# SCH_RAK_Power_module_2023-06-18.net
KiCad netlist of a schematic drawn in EasyEDA
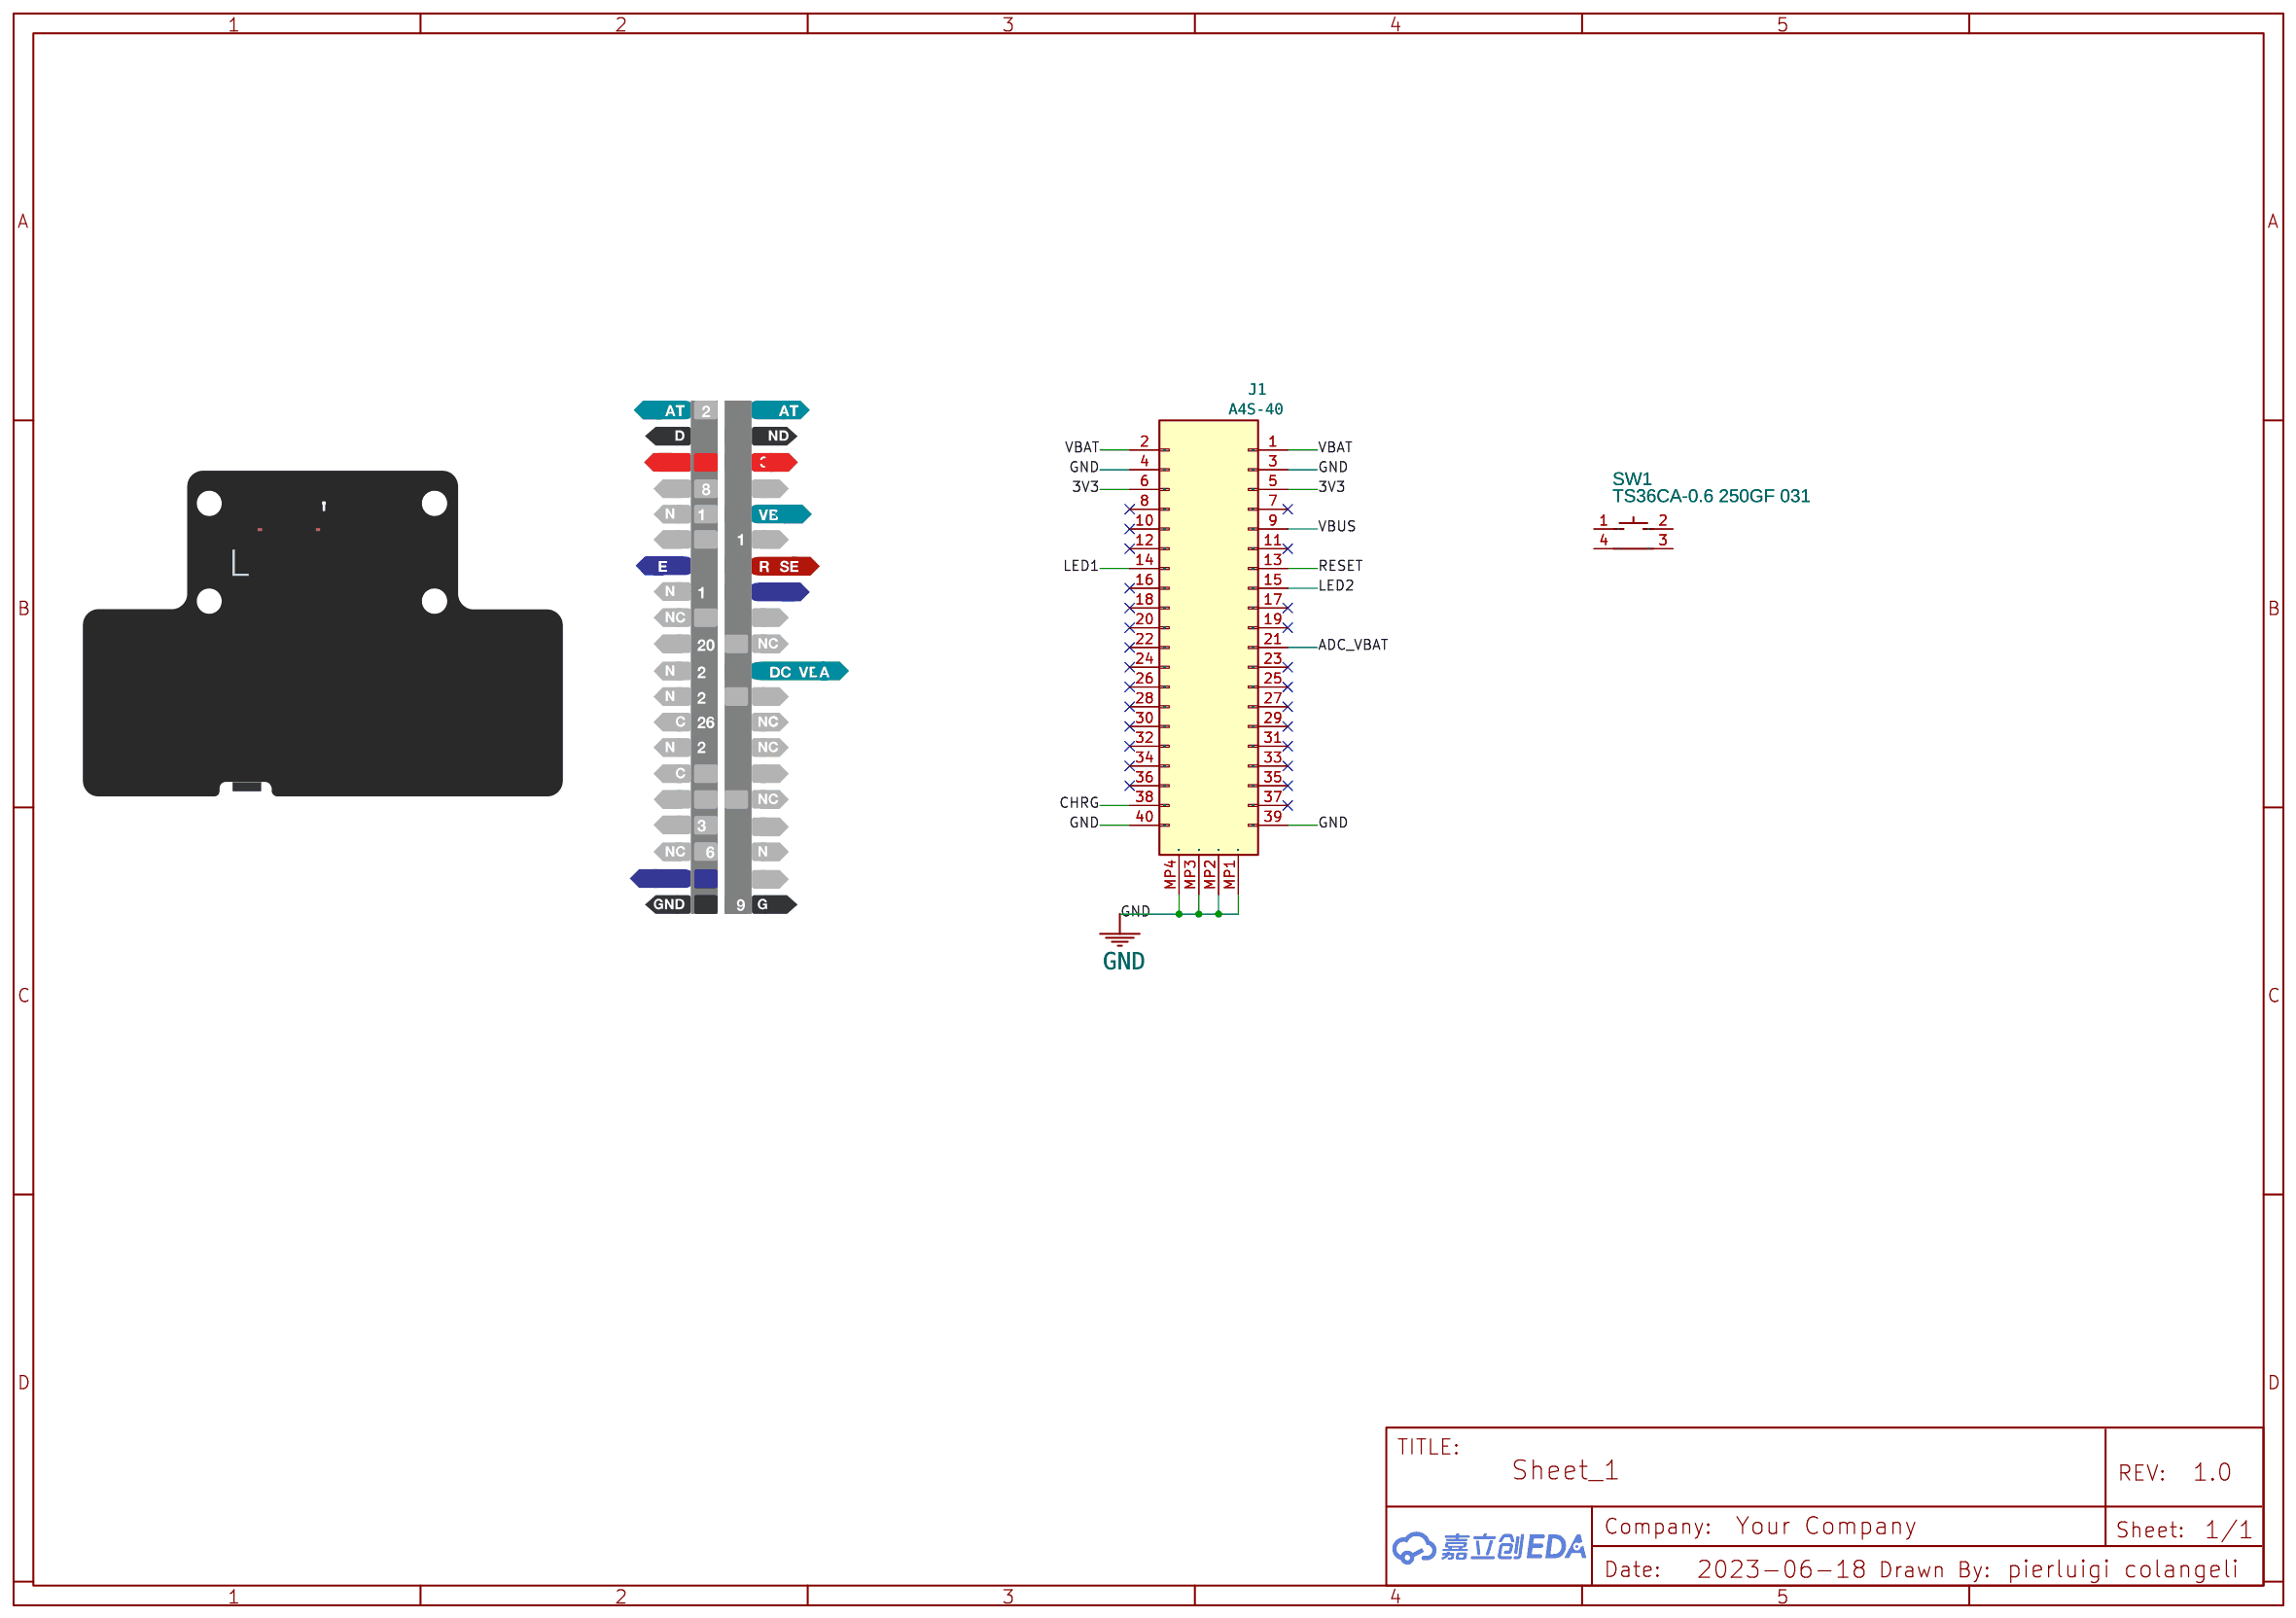
[diagram p0: schematic sheet]

(export (version "E")
  (design (tool "Eeschema 10.0.6"))
  (components
    (comp (ref "J1") (value "A4S-40") (libsource (lib "") (part "Unknown_605_-485")))
    (comp (ref "SW1")
      (value "TS36CA-0.6 250GF 031")
      (fields
        (field (name "BOM_Manufacturer Part") "TS36CA-0.6 250gf 031")
        (field (name "BOM_Supplier Part") "C2906288")
      )
      (libsource (lib "") (part "TS36CA-0.6 250GF 031"))
    )
  )
  (nets
    (net (code "1") (name "/3V3") (class "Default")
      (node (ref "J1") (pin "5") (pinfunction "Pin_5_5") (pintype "unspecified"))
      (node (ref "J1") (pin "6") (pinfunction "Pin_6_6") (pintype "unspecified"))
    )
    (net (code "2") (name "/ADC_VBAT") (class "Default")
      (node (ref "J1") (pin "21") (pinfunction "Pin_21_21") (pintype "unspecified"))
    )
    (net (code "3") (name "/CHRG") (class "Default")
      (node (ref "J1") (pin "38") (pinfunction "Pin_38_38") (pintype "unspecified"))
    )
    (net (code "4") (name "/LED1") (class "Default")
      (node (ref "J1") (pin "14") (pinfunction "Pin_14_14") (pintype "unspecified"))
    )
    (net (code "5") (name "/LED2") (class "Default")
      (node (ref "J1") (pin "15") (pinfunction "Pin_15_15") (pintype "unspecified"))
    )
    (net (code "6") (name "/RESET") (class "Default")
      (node (ref "J1") (pin "13") (pinfunction "Pin_13_13") (pintype "unspecified"))
    )
    (net (code "7") (name "/VBAT") (class "Default")
      (node (ref "J1") (pin "1") (pinfunction "Pin_1_1") (pintype "unspecified"))
      (node (ref "J1") (pin "2") (pinfunction "Pin_2_2") (pintype "unspecified"))
    )
    (net (code "8") (name "/VBUS") (class "Default")
      (node (ref "J1") (pin "9") (pinfunction "Pin_9_9") (pintype "unspecified"))
    )
    (net (code "9") (name "GND") (class "Default")
      (node (ref "J1") (pin "3") (pinfunction "Pin_3_3") (pintype "unspecified"))
      (node (ref "J1") (pin "39") (pinfunction "Pin_39_39") (pintype "unspecified"))
      (node (ref "J1") (pin "4") (pinfunction "Pin_4_4") (pintype "unspecified"))
      (node (ref "J1") (pin "40") (pinfunction "Pin_40_40") (pintype "unspecified"))
      (node (ref "J1") (pin "MP1") (pinfunction "MP1_MP1") (pintype "unspecified"))
      (node (ref "J1") (pin "MP2") (pinfunction "MP2_MP2") (pintype "unspecified"))
      (node (ref "J1") (pin "MP3") (pinfunction "MP3_MP3") (pintype "unspecified"))
      (node (ref "J1") (pin "MP4") (pinfunction "MP4_MP4") (pintype "unspecified"))
    )
    (net (code "10") (name "unconnected-(J1-Pin_7-Pad7)") (class "Default")
      (node (ref "J1") (pin "7") (pinfunction "Pin_7_7") (pintype "unspecified+no_connect"))
    )
    (net (code "11") (name "unconnected-(J1-Pin_8-Pad8)") (class "Default")
      (node (ref "J1") (pin "8") (pinfunction "Pin_8_8") (pintype "unspecified+no_connect"))
    )
    (net (code "12") (name "unconnected-(J1-Pin_10-Pad10)") (class "Default")
      (node (ref "J1") (pin "10") (pinfunction "Pin_10_10") (pintype "unspecified+no_connect"))
    )
    (net (code "13") (name "unconnected-(J1-Pin_11-Pad11)") (class "Default")
      (node (ref "J1") (pin "11") (pinfunction "Pin_11_11") (pintype "unspecified+no_connect"))
    )
    (net (code "14") (name "unconnected-(J1-Pin_12-Pad12)") (class "Default")
      (node (ref "J1") (pin "12") (pinfunction "Pin_12_12") (pintype "unspecified+no_connect"))
    )
    (net (code "15") (name "unconnected-(J1-Pin_16-Pad16)") (class "Default")
      (node (ref "J1") (pin "16") (pinfunction "Pin_16_16") (pintype "unspecified+no_connect"))
    )
    (net (code "16") (name "unconnected-(J1-Pin_17-Pad17)") (class "Default")
      (node (ref "J1") (pin "17") (pinfunction "Pin_17_17") (pintype "unspecified+no_connect"))
    )
    (net (code "17") (name "unconnected-(J1-Pin_18-Pad18)") (class "Default")
      (node (ref "J1") (pin "18") (pinfunction "Pin_18_18") (pintype "unspecified+no_connect"))
    )
    (net (code "18") (name "unconnected-(J1-Pin_19-Pad19)") (class "Default")
      (node (ref "J1") (pin "19") (pinfunction "Pin_19_19") (pintype "unspecified+no_connect"))
    )
    (net (code "19") (name "unconnected-(J1-Pin_20-Pad20)") (class "Default")
      (node (ref "J1") (pin "20") (pinfunction "Pin_20_20") (pintype "unspecified+no_connect"))
    )
    (net (code "20") (name "unconnected-(J1-Pin_22-Pad22)") (class "Default")
      (node (ref "J1") (pin "22") (pinfunction "Pin_22_22") (pintype "unspecified+no_connect"))
    )
    (net (code "21") (name "unconnected-(J1-Pin_23-Pad23)") (class "Default")
      (node (ref "J1") (pin "23") (pinfunction "Pin_23_23") (pintype "unspecified+no_connect"))
    )
    (net (code "22") (name "unconnected-(J1-Pin_24-Pad24)") (class "Default")
      (node (ref "J1") (pin "24") (pinfunction "Pin_24_24") (pintype "unspecified+no_connect"))
    )
    (net (code "23") (name "unconnected-(J1-Pin_25-Pad25)") (class "Default")
      (node (ref "J1") (pin "25") (pinfunction "Pin_25_25") (pintype "unspecified+no_connect"))
    )
    (net (code "24") (name "unconnected-(J1-Pin_26-Pad26)") (class "Default")
      (node (ref "J1") (pin "26") (pinfunction "Pin_26_26") (pintype "unspecified+no_connect"))
    )
    (net (code "25") (name "unconnected-(J1-Pin_27-Pad27)") (class "Default")
      (node (ref "J1") (pin "27") (pinfunction "Pin_27_27") (pintype "unspecified+no_connect"))
    )
    (net (code "26") (name "unconnected-(J1-Pin_28-Pad28)") (class "Default")
      (node (ref "J1") (pin "28") (pinfunction "Pin_28_28") (pintype "unspecified+no_connect"))
    )
    (net (code "27") (name "unconnected-(J1-Pin_29-Pad29)") (class "Default")
      (node (ref "J1") (pin "29") (pinfunction "Pin_29_29") (pintype "unspecified+no_connect"))
    )
    (net (code "28") (name "unconnected-(J1-Pin_30-Pad30)") (class "Default")
      (node (ref "J1") (pin "30") (pinfunction "Pin_30_30") (pintype "unspecified+no_connect"))
    )
    (net (code "29") (name "unconnected-(J1-Pin_31-Pad31)") (class "Default")
      (node (ref "J1") (pin "31") (pinfunction "Pin_31_31") (pintype "unspecified+no_connect"))
    )
    (net (code "30") (name "unconnected-(J1-Pin_32-Pad32)") (class "Default")
      (node (ref "J1") (pin "32") (pinfunction "Pin_32_32") (pintype "unspecified+no_connect"))
    )
    (net (code "31") (name "unconnected-(J1-Pin_33-Pad33)") (class "Default")
      (node (ref "J1") (pin "33") (pinfunction "Pin_33_33") (pintype "unspecified+no_connect"))
    )
    (net (code "32") (name "unconnected-(J1-Pin_34-Pad34)") (class "Default")
      (node (ref "J1") (pin "34") (pinfunction "Pin_34_34") (pintype "unspecified+no_connect"))
    )
    (net (code "33") (name "unconnected-(J1-Pin_35-Pad35)") (class "Default")
      (node (ref "J1") (pin "35") (pinfunction "Pin_35_35") (pintype "unspecified+no_connect"))
    )
    (net (code "34") (name "unconnected-(J1-Pin_36-Pad36)") (class "Default")
      (node (ref "J1") (pin "36") (pinfunction "Pin_36_36") (pintype "unspecified+no_connect"))
    )
    (net (code "35") (name "unconnected-(J1-Pin_37-Pad37)") (class "Default")
      (node (ref "J1") (pin "37") (pinfunction "Pin_37_37") (pintype "unspecified+no_connect"))
    )
    (net (code "36") (name "unconnected-(SW1-Pad1)") (class "Default")
      (node (ref "SW1") (pin "1") (pinfunction "1_1") (pintype "unspecified"))
    )
    (net (code "37") (name "unconnected-(SW1-Pad2)") (class "Default")
      (node (ref "SW1") (pin "2") (pinfunction "2_2") (pintype "unspecified"))
    )
    (net (code "38") (name "unconnected-(SW1-Pad3)") (class "Default")
      (node (ref "SW1") (pin "3") (pinfunction "3_3") (pintype "unspecified"))
    )
    (net (code "39") (name "unconnected-(SW1-Pad4)") (class "Default")
      (node (ref "SW1") (pin "4") (pinfunction "4_4") (pintype "unspecified"))
    )
  )
)
